# old_amplifer_can_delete.net
KiCad netlist of a schematic drawn in Altium Designer
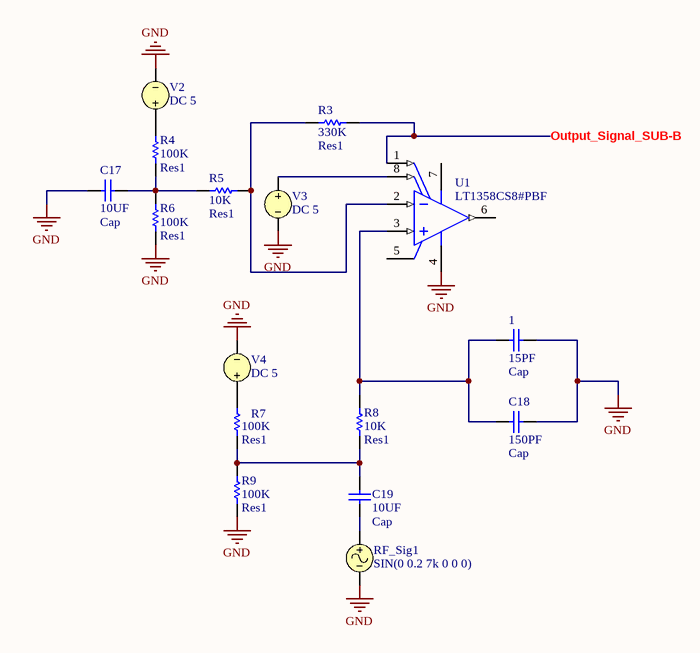
[diagram p0: old amplifer can delete.SchDoc]

(export (version "E")
  (design (tool "Eeschema 10.0.6"))
  (components
    (comp (ref "1")
      (value "Cap")
      (footprint "RADIAL-0.1")
      (description "Capacitor")
      (fields
        (field (name "ALTIUM_VALUE") "15PF")
        (field (name "MANUFACTURER PART NUMBER") "K150J15C0GF5TL2")
        (field (name "PUBLISHER") "Altium Limited")
      )
      (libsource (lib "ECE295-Capacitors-TH") (part "CAP CER 15PF 50V C0G/NP0 RADIAL"))
    )
    (comp (ref "C17")
      (value "Cap")
      (footprint "RADIAL-0.1")
      (description "Capacitor")
      (fields
        (field (name "ALTIUM_VALUE") "10UF")
        (field (name "MANUFACTURER PART NUMBER") "ESK106M063AC3FA")
        (field (name "PUBLISHER") "Altium Limited")
      )
      (libsource (lib "ECE295-Capacitors-TH") (part "CAP ALUM 10UF 20% 63V RADIAL"))
    )
    (comp (ref "C18")
      (value "Cap")
      (footprint "RADIAL-0.1")
      (description "Capacitor")
      (fields
        (field (name "ALTIUM_VALUE") "150PF")
        (field (name "MANUFACTURER PART NUMBER") "K151J15C0GF53L2")
        (field (name "PUBLISHER") "Altium Limited")
      )
      (libsource (lib "ECE295-Capacitors-TH") (part "CAP CER 150PF 50V C0G/NP0 RADIAL"))
    )
    (comp (ref "C19")
      (value "Cap")
      (footprint "RADIAL-0.1")
      (description "Capacitor")
      (fields
        (field (name "ALTIUM_VALUE") "10UF")
        (field (name "MANUFACTURER PART NUMBER") "ESK106M063AC3FA")
        (field (name "PUBLISHER") "Altium Limited")
      )
      (libsource (lib "ECE295-Capacitors-TH") (part "CAP ALUM 10UF 20% 63V RADIAL"))
    )
    (comp (ref "R3")
      (value "Res1")
      (footprint "AXIAL-0.1-RES")
      (description "Resistor")
      (fields
        (field (name "ALTIUM_VALUE") "330K")
        (field (name "MANUFACTURER PART NUMBER") "CFR-25JB-52-330K")
        (field (name "TOLERANCE") "0.05")
        (field (name "PUBLISHER") "Altium Limited")
      )
      (libsource (lib "ECE295-Resistors-TH") (part "RES 330K OHM 5% 1/4W AXIAL"))
    )
    (comp (ref "R4")
      (value "Res1")
      (footprint "AXIAL-0.1-RES")
      (description "Resistor")
      (fields
        (field (name "ALTIUM_VALUE") "100K")
        (field (name "MANUFACTURER PART NUMBER") "CFR-25JB-52-100K")
        (field (name "TOLERANCE") "0.05")
        (field (name "PUBLISHER") "Altium Limited")
      )
      (libsource (lib "ECE295-Resistors-TH") (part "RES 100K OHM 5% 1/4W AXIAL"))
    )
    (comp (ref "R5")
      (value "Res1")
      (footprint "AXIAL-0.1-RES")
      (description "Resistor")
      (fields
        (field (name "ALTIUM_VALUE") "10K")
        (field (name "MANUFACTURER PART NUMBER") "CFR-25JB-52-10K")
        (field (name "TOLERANCE") "0.05")
        (field (name "PUBLISHER") "Altium Limited")
      )
      (libsource (lib "ECE295-Resistors-TH") (part "RES 10K OHM 5% 1/4W AXIAL"))
    )
    (comp (ref "R6")
      (value "Res1")
      (footprint "AXIAL-0.1-RES")
      (description "Resistor")
      (fields
        (field (name "ALTIUM_VALUE") "100K")
        (field (name "MANUFACTURER PART NUMBER") "CFR-25JB-52-100K")
        (field (name "TOLERANCE") "0.05")
        (field (name "PUBLISHER") "Altium Limited")
      )
      (libsource (lib "ECE295-Resistors-TH") (part "RES 100K OHM 5% 1/4W AXIAL"))
    )
    (comp (ref "R7")
      (value "Res1")
      (footprint "AXIAL-0.1-RES")
      (description "Resistor")
      (fields
        (field (name "ALTIUM_VALUE") "100K")
        (field (name "MANUFACTURER PART NUMBER") "CFR-25JB-52-100K")
        (field (name "TOLERANCE") "0.05")
        (field (name "PUBLISHER") "Altium Limited")
      )
      (libsource (lib "ECE295-Resistors-TH") (part "RES 100K OHM 5% 1/4W AXIAL"))
    )
    (comp (ref "R8")
      (value "Res1")
      (footprint "AXIAL-0.1-RES")
      (description "Resistor")
      (fields
        (field (name "ALTIUM_VALUE") "10K")
        (field (name "MANUFACTURER PART NUMBER") "CFR-25JB-52-10K")
        (field (name "TOLERANCE") "0.05")
        (field (name "PUBLISHER") "Altium Limited")
      )
      (libsource (lib "ECE295-Resistors-TH") (part "RES 10K OHM 5% 1/4W AXIAL"))
    )
    (comp (ref "R9")
      (value "Res1")
      (footprint "AXIAL-0.1-RES")
      (description "Resistor")
      (fields
        (field (name "ALTIUM_VALUE") "100K")
        (field (name "MANUFACTURER PART NUMBER") "CFR-25JB-52-100K")
        (field (name "TOLERANCE") "0.05")
        (field (name "PUBLISHER") "Altium Limited")
      )
      (libsource (lib "ECE295-Resistors-TH") (part "RES 100K OHM 5% 1/4W AXIAL"))
    )
    (comp (ref "RF_Sig1")
      (value "SIN(0 0.2 7k 0 0 0)")
      (description "Sinusoidal Voltage Source")
      (fields (field (name "PUBLISHER") "Altium Limited"))
      (libsource (lib "Simulation Generic Components") (part "VSIN"))
    )
    (comp (ref "U1")
      (value "LT1358CS8#PBF")
      (footprint "LT-S8-8_M")
      (fields
        (field (name "MANUFACTURER") "Linear Technology")
        (field (name "LINEAR TECHNOLOGY PART NUMBER") "LT1358")
      )
      (libsource (lib "Altium Content Vault") (part "LT-LT135X-LT136X-8"))
    )
    (comp (ref "V2")
      (value "DC 5")
      (description "Voltage Source")
      (fields (field (name "PUBLISHER") "Altium Limited"))
      (libsource (lib "Simulation Generic Components") (part "VSRC"))
    )
    (comp (ref "V3")
      (value "DC 5")
      (description "Voltage Source")
      (fields (field (name "PUBLISHER") "Altium Limited"))
      (libsource (lib "Simulation Generic Components") (part "VSRC"))
    )
    (comp (ref "V4")
      (value "DC 5")
      (description "Voltage Source")
      (fields (field (name "PUBLISHER") "Altium Limited"))
      (libsource (lib "Simulation Generic Components") (part "VSRC"))
    )
  )
  (nets
    (net (code "1") (name "/Output_Signal_SUB-B") (class "Default")
      (node (ref "R3") (pin "2") (pinfunction "2_2") (pintype "passive"))
      (node (ref "U1") (pin "1") (pinfunction "NULL_1") (pintype "input"))
    )
    (net (code "2") (name "GND") (class "Default")
      (node (ref "1") (pin "2") (pinfunction "2_2") (pintype "passive"))
      (node (ref "C17") (pin "1") (pinfunction "1_1") (pintype "passive"))
      (node (ref "C18") (pin "1") (pinfunction "1_1") (pintype "passive"))
      (node (ref "R6") (pin "1") (pinfunction "1_1") (pintype "passive"))
      (node (ref "R9") (pin "1") (pinfunction "1_1") (pintype "passive"))
      (node (ref "RF_Sig1") (pin "2") (pinfunction "2_2") (pintype "passive"))
      (node (ref "U1") (pin "4") (pinfunction "V-_4") (pintype "power_in"))
      (node (ref "V2") (pin "2") (pinfunction "2_2") (pintype "passive"))
      (node (ref "V3") (pin "2") (pinfunction "2_2") (pintype "passive"))
      (node (ref "V4") (pin "2") (pinfunction "2_2") (pintype "passive"))
    )
    (net (code "3") (name "Net-(C17-Pad2)") (class "Default")
      (node (ref "C17") (pin "2") (pinfunction "2_2") (pintype "passive"))
      (node (ref "R4") (pin "1") (pinfunction "1_1") (pintype "passive"))
      (node (ref "R5") (pin "1") (pinfunction "1_1") (pintype "passive"))
      (node (ref "R6") (pin "2") (pinfunction "2_2") (pintype "passive"))
    )
    (net (code "4") (name "Net-(C19-Pad1)") (class "Default")
      (node (ref "C19") (pin "1") (pinfunction "1_1") (pintype "passive"))
      (node (ref "RF_Sig1") (pin "1") (pinfunction "1_1") (pintype "passive"))
    )
    (net (code "5") (name "Net-(C19-Pad2)") (class "Default")
      (node (ref "C19") (pin "2") (pinfunction "2_2") (pintype "passive"))
      (node (ref "R7") (pin "1") (pinfunction "1_1") (pintype "passive"))
      (node (ref "R8") (pin "1") (pinfunction "1_1") (pintype "passive"))
      (node (ref "R9") (pin "2") (pinfunction "2_2") (pintype "passive"))
    )
    (net (code "6") (name "Net-(R4-Pad2)") (class "Default")
      (node (ref "R4") (pin "2") (pinfunction "2_2") (pintype "passive"))
      (node (ref "V2") (pin "1") (pinfunction "1_1") (pintype "passive"))
    )
    (net (code "7") (name "Net-(R7-Pad2)") (class "Default")
      (node (ref "R7") (pin "2") (pinfunction "2_2") (pintype "passive"))
      (node (ref "V4") (pin "1") (pinfunction "1_1") (pintype "passive"))
    )
    (net (code "8") (name "Net-(U1-+IN)") (class "Default")
      (node (ref "1") (pin "1") (pinfunction "1_1") (pintype "passive"))
      (node (ref "C18") (pin "2") (pinfunction "2_2") (pintype "passive"))
      (node (ref "R8") (pin "2") (pinfunction "2_2") (pintype "passive"))
      (node (ref "U1") (pin "3") (pinfunction "+IN_3") (pintype "input"))
    )
    (net (code "9") (name "Net-(U1--IN)") (class "Default")
      (node (ref "R3") (pin "1") (pinfunction "1_1") (pintype "passive"))
      (node (ref "R5") (pin "2") (pinfunction "2_2") (pintype "passive"))
      (node (ref "U1") (pin "2") (pinfunction "-IN_2") (pintype "input"))
    )
    (net (code "10") (name "Net-(U1-NULL-Pad8)") (class "Default")
      (node (ref "U1") (pin "8") (pinfunction "NULL_8") (pintype "input"))
      (node (ref "V3") (pin "1") (pinfunction "1_1") (pintype "passive"))
    )
    (net (code "11") (name "unconnected-(U1-NC-Pad5)") (class "Default")
      (node (ref "U1") (pin "5") (pinfunction "NC_5") (pintype "passive"))
    )
    (net (code "12") (name "unconnected-(U1-V+-Pad7)") (class "Default")
      (node (ref "U1") (pin "7") (pinfunction "V+_7") (pintype "power_in"))
    )
    (net (code "13") (name "unconnected-(U1-VOUT-Pad6)") (class "Default")
      (node (ref "U1") (pin "6") (pinfunction "VOUT_6") (pintype "output"))
    )
  )
)
